# 202011AWSNP03.net
KiCad netlist of a schematic drawn in Altium Designer
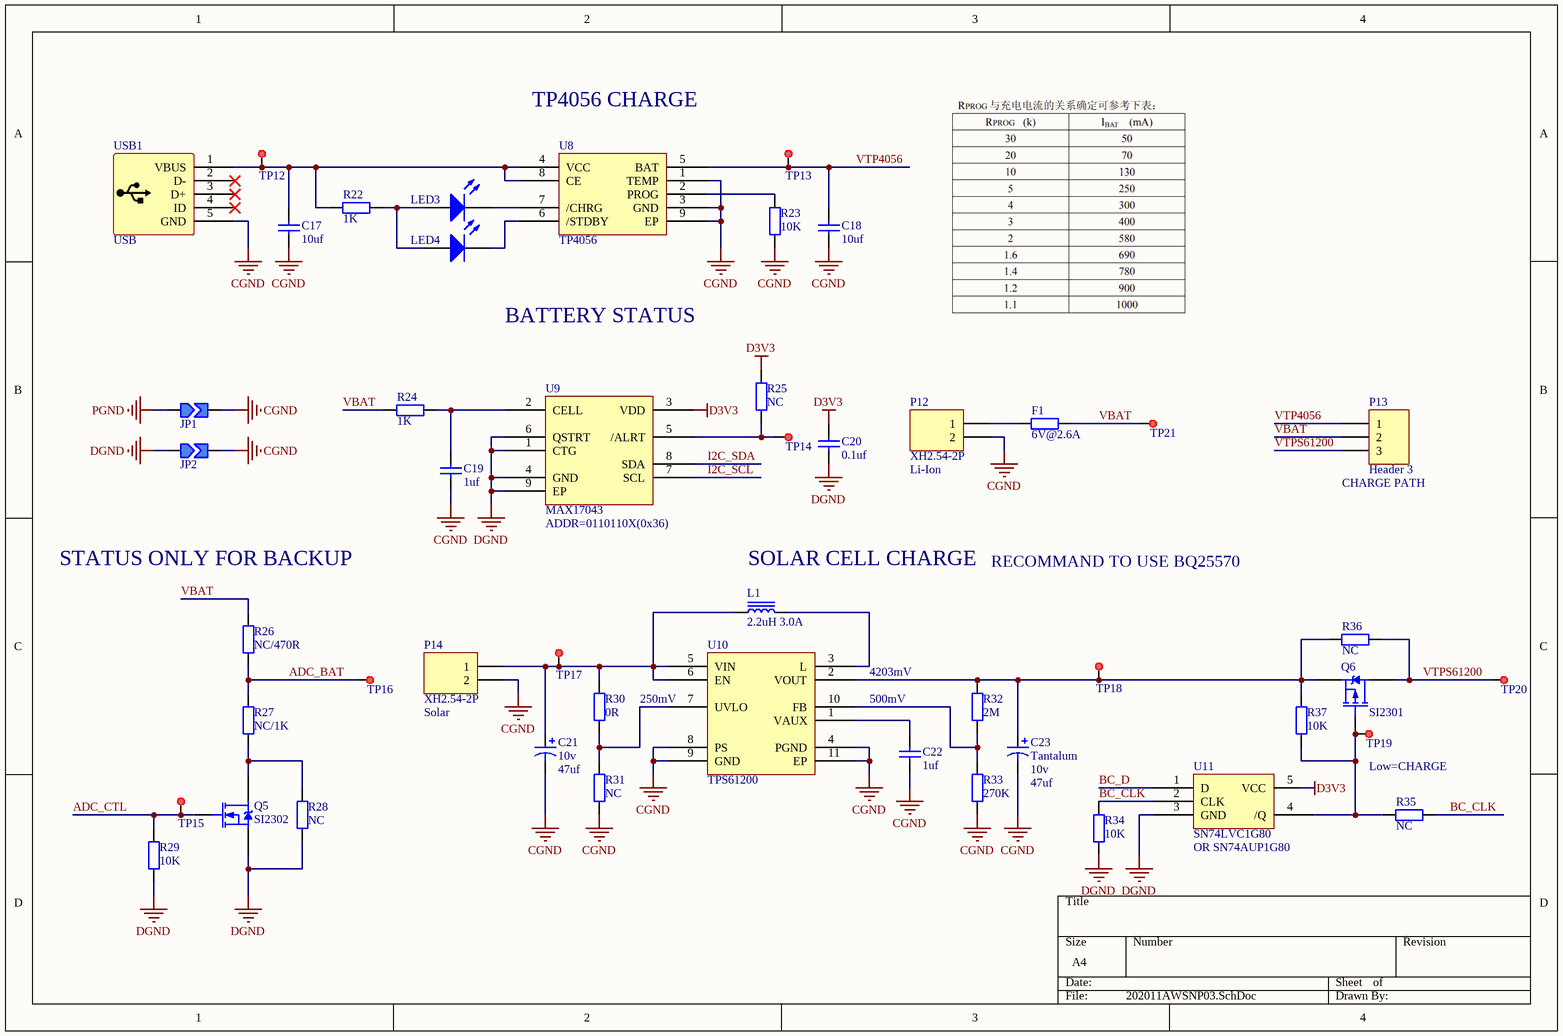
[diagram p0: 202011AWSNP03.SchDoc]

(export (version "E")
  (design (tool "Eeschema 10.0.6"))
  (components
    (comp (ref "C17")
      (value "10uf")
      (footprint "C0805")
      (fields (field (name "Comment") "Cap"))
      (libsource (lib "carrot_lib") (part "Cap"))
    )
    (comp (ref "C18")
      (value "10uf")
      (footprint "C0805")
      (fields (field (name "Comment") "Cap"))
      (libsource (lib "carrot_lib") (part "Cap"))
    )
    (comp (ref "C19")
      (value "1uf")
      (footprint "C0805")
      (fields (field (name "Comment") "Cap"))
      (libsource (lib "carrot_lib") (part "Cap"))
    )
    (comp (ref "C20")
      (value "0.1uf")
      (footprint "C0805")
      (fields (field (name "Comment") "Cap"))
      (libsource (lib "carrot_lib") (part "Cap"))
    )
    (comp (ref "C21")
      (value "47uf")
      (footprint "C4X5.4-SMD")
      (fields (field (name "VOLTAGE") "10v") (field (name "Comment") "Cap2"))
      (libsource (lib "carrot_lib") (part "Cap2"))
    )
    (comp (ref "C22")
      (value "1uf")
      (footprint "C0805")
      (fields (field (name "Comment") "Cap"))
      (libsource (lib "carrot_lib") (part "Cap"))
    )
    (comp (ref "C23")
      (value "Tantalum")
      (footprint "C1210T-3528B")
      (fields (field (name "VOLTAGE") "10v") (field (name "ALTIUM_VALUE") "47uf"))
      (libsource (lib "carrot_lib") (part "Cap-Tantalum"))
    )
    (comp (ref "F1")
      (value "6V@2.6A")
      (footprint "F1812")
      (fields (field (name "Comment") "Fuse"))
      (libsource (lib "carrot_lib") (part "Fuse"))
    )
    (comp (ref "JP1") (value "Jumper") (footprint "Jumper-2") (libsource (lib "carrot_lib") (part "Jumper")))
    (comp (ref "JP2") (value "Jumper") (footprint "Jumper-2") (libsource (lib "carrot_lib") (part "Jumper")))
    (comp (ref "L1")
      (value "2.2uH 3.0A")
      (footprint "L04042")
      (description "Magnetic-Core Inductor")
      (fields (field (name "Comment") "Inductor Iron"))
      (libsource (lib "carrot_lib") (part "Inductor Iron"))
    )
    (comp (ref "LED3") (value "LED") (footprint "LED1206") (libsource (lib "carrot_lib") (part "LED")))
    (comp (ref "LED4") (value "LED") (footprint "LED1206") (libsource (lib "carrot_lib") (part "LED")))
    (comp (ref "P12")
      (value "XH2.54-2P")
      (footprint "XH2.54-2P")
      (libsource (lib "carrot_lib") (part "XH2.54-2P"))
    )
    (comp (ref "P13")
      (value "Header 3")
      (footprint "HDR1X3")
      (description "Header, 3-Pin")
      (fields (field (name "PUBLISHER") "Altium Limited"))
      (libsource (lib "Miscellaneous Connectors") (part "Header 3"))
    )
    (comp (ref "P14")
      (value "XH2.54-2P")
      (footprint "XH2.54-2P")
      (libsource (lib "carrot_lib") (part "XH2.54-2P"))
    )
    (comp (ref "Q5")
      (value "SI2302")
      (footprint "SI2302-SOT23")
      (description "N-Channel 20 V (D-S) MOSFET")
      (libsource (lib "carrot_lib") (part "SI2302"))
    )
    (comp (ref "Q6")
      (value "SI2301")
      (footprint "SI2301-SOT23")
      (description "P-Channel 20 V (D-S) MOSFET")
      (libsource (lib "carrot_lib") (part "SI2301"))
    )
    (comp (ref "R22")
      (value "1K")
      (footprint "R0805")
      (description "电阻")
      (fields (field (name "Comment") "Res"))
      (libsource (lib "carrot_lib") (part "Res"))
    )
    (comp (ref "R23")
      (value "10K")
      (footprint "R0805")
      (description "电阻")
      (fields (field (name "Comment") "Res"))
      (libsource (lib "") (part "Res_2"))
    )
    (comp (ref "R24")
      (value "1K")
      (footprint "R0805")
      (description "电阻")
      (fields (field (name "Comment") "Res"))
      (libsource (lib "carrot_lib") (part "Res"))
    )
    (comp (ref "R25")
      (value "NC")
      (footprint "R0805")
      (description "电阻")
      (fields (field (name "Comment") "Res"))
      (libsource (lib "") (part "Res_2"))
    )
    (comp (ref "R26")
      (value "NC/470R")
      (footprint "R0805")
      (description "电阻")
      (fields (field (name "Comment") "Res"))
      (libsource (lib "") (part "Res_1"))
    )
    (comp (ref "R27")
      (value "NC/1K")
      (footprint "R0805")
      (description "电阻")
      (fields (field (name "Comment") "Res"))
      (libsource (lib "") (part "Res_1"))
    )
    (comp (ref "R28")
      (value "NC")
      (footprint "R0805")
      (description "电阻")
      (fields (field (name "Comment") "Res"))
      (libsource (lib "") (part "Res_1"))
    )
    (comp (ref "R29")
      (value "10K")
      (footprint "R0805")
      (description "电阻")
      (fields (field (name "Comment") "Res"))
      (libsource (lib "") (part "Res_1"))
    )
    (comp (ref "R30")
      (value "0R")
      (footprint "R0805")
      (description "电阻")
      (fields (field (name "Comment") "Res"))
      (libsource (lib "") (part "Res_2"))
    )
    (comp (ref "R31")
      (value "NC")
      (footprint "R0805")
      (description "电阻")
      (fields (field (name "Comment") "Res"))
      (libsource (lib "") (part "Res_2"))
    )
    (comp (ref "R32")
      (value "2M")
      (footprint "R0805")
      (description "电阻")
      (fields (field (name "Comment") "Res"))
      (libsource (lib "") (part "Res_2"))
    )
    (comp (ref "R33")
      (value "270K")
      (footprint "R0805")
      (description "电阻")
      (fields (field (name "Comment") "Res"))
      (libsource (lib "") (part "Res_2"))
    )
    (comp (ref "R34")
      (value "10K")
      (footprint "R0805")
      (description "电阻")
      (fields (field (name "Comment") "Res"))
      (libsource (lib "carrot_lib") (part "Res"))
    )
    (comp (ref "R35")
      (value "NC")
      (footprint "R0805")
      (description "电阻")
      (fields (field (name "Comment") "Res"))
      (libsource (lib "") (part "Res_2"))
    )
    (comp (ref "R36")
      (value "NC")
      (footprint "R0805")
      (description "电阻")
      (fields (field (name "Comment") "Res"))
      (libsource (lib "") (part "Res_2"))
    )
    (comp (ref "R37")
      (value "10K")
      (footprint "R0805")
      (description "电阻")
      (fields (field (name "Comment") "Res"))
      (libsource (lib "carrot_lib") (part "Res"))
    )
    (comp (ref "TP12")
      (value "TestPoint")
      (footprint "TestPoint-R30")
      (description "测试点")
      (libsource (lib "carrot_lib") (part "TestPoint"))
    )
    (comp (ref "TP13")
      (value "TestPoint")
      (footprint "TestPoint-R30")
      (description "测试点")
      (libsource (lib "carrot_lib") (part "TestPoint"))
    )
    (comp (ref "TP14")
      (value "TestPoint")
      (footprint "TestPoint-R30")
      (description "测试点")
      (libsource (lib "carrot_lib") (part "TestPoint"))
    )
    (comp (ref "TP15")
      (value "TestPoint")
      (footprint "TestPoint-R30")
      (description "测试点")
      (libsource (lib "carrot_lib") (part "TestPoint"))
    )
    (comp (ref "TP16")
      (value "TestPoint")
      (footprint "TestPoint-R30")
      (description "测试点")
      (libsource (lib "carrot_lib") (part "TestPoint"))
    )
    (comp (ref "TP17")
      (value "TestPoint")
      (footprint "TestPoint-R30")
      (description "测试点")
      (libsource (lib "carrot_lib") (part "TestPoint"))
    )
    (comp (ref "TP18")
      (value "TestPoint")
      (footprint "TestPoint-R30")
      (description "测试点")
      (libsource (lib "carrot_lib") (part "TestPoint"))
    )
    (comp (ref "TP19")
      (value "TestPoint")
      (footprint "TestPoint-R30")
      (description "测试点")
      (libsource (lib "carrot_lib") (part "TestPoint"))
    )
    (comp (ref "TP20")
      (value "TestPoint")
      (footprint "TestPoint-R30")
      (description "测试点")
      (libsource (lib "carrot_lib") (part "TestPoint"))
    )
    (comp (ref "TP21")
      (value "TestPoint")
      (footprint "TestPoint-R30")
      (description "测试点")
      (libsource (lib "carrot_lib") (part "TestPoint"))
    )
    (comp (ref "U8")
      (value "TP4056")
      (footprint "TP4056-SOIC8")
      (description "1A 线性锂离子电池充电器")
      (libsource (lib "carrot_lib") (part "TP4056"))
    )
    (comp (ref "U9")
      (value "MAX17043")
      (footprint "MAX17043-TDFN8")
      (description "1-Cell/2-Cell Fuel Gauge with ModelGauge and Low-Battery Alert")
      (libsource (lib "carrot_lib") (part "MAX17043"))
    )
    (comp (ref "U10")
      (value "TPS61200")
      (footprint "TPS61200-VSON10")
      (description "TPS61200x Low Input Voltage Synchronous Boost Converter With 1.3-A Switches")
      (libsource (lib "carrot_lib") (part "TPS61200"))
    )
    (comp (ref "U11")
      (value "SN74LVC1G80")
      (footprint "SN74LVC1G80-SC70")
      (description "Single Positive-Edge-Triggered D-Type Flip-Flop")
      (libsource (lib "carrot_lib") (part "SN74LVC1G80"))
    )
    (comp (ref "USB1") (value "USB") (footprint "USB-Mini-SMT") (libsource (lib "carrot_lib") (part "USB")))
  )
  (nets
    (net (code "1") (name "/ADC_BAT") (class "Default")
      (node (ref "R26") (pin "1") (pinfunction "1_1") (pintype "passive"))
      (node (ref "R27") (pin "2") (pinfunction "2_2") (pintype "passive"))
      (node (ref "TP16") (pin "1") (pinfunction "1_1") (pintype "passive"))
    )
    (net (code "2") (name "/ADC_CTL") (class "Default")
      (node (ref "Q5") (pin "1") (pinfunction "G_1") (pintype "passive"))
      (node (ref "R29") (pin "2") (pinfunction "2_2") (pintype "passive"))
      (node (ref "TP15") (pin "1") (pinfunction "1_1") (pintype "passive"))
    )
    (net (code "3") (name "/BC_CLK") (class "Default")
      (node (ref "R34") (pin "1") (pinfunction "1_1") (pintype "passive"))
      (node (ref "R35") (pin "1") (pinfunction "1_1") (pintype "passive"))
      (node (ref "U11") (pin "2") (pinfunction "CLK_2") (pintype "passive"))
    )
    (net (code "4") (name "/BC_D") (class "Default")
      (node (ref "U11") (pin "1") (pinfunction "D_1") (pintype "passive"))
    )
    (net (code "5") (name "/I2C_SCL") (class "Default")
      (node (ref "U9") (pin "7") (pinfunction "SCL_7") (pintype "passive"))
    )
    (net (code "6") (name "/I2C_SDA") (class "Default")
      (node (ref "U9") (pin "8") (pinfunction "SDA_8") (pintype "passive"))
    )
    (net (code "7") (name "/VBAT") (class "Default")
      (node (ref "F1") (pin "2") (pinfunction "2_2") (pintype "passive"))
      (node (ref "P13") (pin "2") (pinfunction "2_2") (pintype "passive"))
      (node (ref "R24") (pin "2") (pinfunction "2_2") (pintype "passive"))
      (node (ref "R26") (pin "2") (pinfunction "2_2") (pintype "passive"))
      (node (ref "TP21") (pin "1") (pinfunction "1_1") (pintype "passive"))
    )
    (net (code "8") (name "/VTP4056") (class "Default")
      (node (ref "C18") (pin "2") (pinfunction "2_2") (pintype "passive"))
      (node (ref "P13") (pin "1") (pinfunction "1_1") (pintype "passive"))
      (node (ref "TP13") (pin "1") (pinfunction "1_1") (pintype "passive"))
      (node (ref "U8") (pin "5") (pinfunction "BAT_5") (pintype "passive"))
    )
    (net (code "9") (name "/VTPS61200") (class "Default")
      (node (ref "P13") (pin "3") (pinfunction "3_3") (pintype "passive"))
      (node (ref "Q6") (pin "3") (pinfunction "D_3") (pintype "passive"))
      (node (ref "R36") (pin "1") (pinfunction "1_1") (pintype "passive"))
      (node (ref "TP20") (pin "1") (pinfunction "1_1") (pintype "passive"))
    )
    (net (code "10") (name "CGND") (class "Default")
      (node (ref "C17") (pin "1") (pinfunction "1_1") (pintype "passive"))
      (node (ref "C18") (pin "1") (pinfunction "1_1") (pintype "passive"))
      (node (ref "C19") (pin "1") (pinfunction "1_1") (pintype "passive"))
      (node (ref "C21") (pin "2") (pinfunction "2_2") (pintype "passive"))
      (node (ref "C22") (pin "1") (pinfunction "1_1") (pintype "passive"))
      (node (ref "C23") (pin "2") (pinfunction "2_2") (pintype "passive"))
      (node (ref "JP1") (pin "2") (pinfunction "2_2") (pintype "passive"))
      (node (ref "JP2") (pin "2") (pinfunction "2_2") (pintype "passive"))
      (node (ref "P12") (pin "2") (pinfunction "2_2") (pintype "passive"))
      (node (ref "P14") (pin "2") (pinfunction "2_2") (pintype "passive"))
      (node (ref "R23") (pin "2") (pinfunction "2_2") (pintype "passive"))
      (node (ref "R31") (pin "2") (pinfunction "2_2") (pintype "passive"))
      (node (ref "R33") (pin "2") (pinfunction "2_2") (pintype "passive"))
      (node (ref "U10") (pin "11") (pinfunction "EP_11") (pintype "passive"))
      (node (ref "U10") (pin "4") (pinfunction "PGND_4") (pintype "passive"))
      (node (ref "U10") (pin "8") (pinfunction "PS_8") (pintype "passive"))
      (node (ref "U10") (pin "9") (pinfunction "GND_9") (pintype "passive"))
      (node (ref "U8") (pin "1") (pinfunction "TEMP_1") (pintype "passive"))
      (node (ref "U8") (pin "3") (pinfunction "GND_3") (pintype "passive"))
      (node (ref "U8") (pin "9") (pinfunction "EP_9") (pintype "passive"))
      (node (ref "USB1") (pin "5") (pinfunction "GND_5") (pintype "passive"))
    )
    (net (code "11") (name "D3V3") (class "Default")
      (node (ref "C20") (pin "2") (pinfunction "2_2") (pintype "passive"))
      (node (ref "R25") (pin "1") (pinfunction "1_1") (pintype "passive"))
      (node (ref "U11") (pin "5") (pinfunction "VCC_5") (pintype "passive"))
      (node (ref "U9") (pin "3") (pinfunction "VDD_3") (pintype "passive"))
    )
    (net (code "12") (name "DGND") (class "Default")
      (node (ref "C20") (pin "1") (pinfunction "1_1") (pintype "passive"))
      (node (ref "JP2") (pin "1") (pinfunction "1_1") (pintype "passive"))
      (node (ref "Q5") (pin "2") (pinfunction "S_2") (pintype "passive"))
      (node (ref "R28") (pin "1") (pinfunction "1_1") (pintype "passive"))
      (node (ref "R29") (pin "1") (pinfunction "1_1") (pintype "passive"))
      (node (ref "R34") (pin "2") (pinfunction "2_2") (pintype "passive"))
      (node (ref "U11") (pin "3") (pinfunction "GND_3") (pintype "passive"))
      (node (ref "U9") (pin "1") (pinfunction "CTG_1") (pintype "passive"))
      (node (ref "U9") (pin "4") (pinfunction "GND_4") (pintype "passive"))
      (node (ref "U9") (pin "6") (pinfunction "QSTRT_6") (pintype "passive"))
      (node (ref "U9") (pin "9") (pinfunction "EP_9") (pintype "passive"))
    )
    (net (code "13") (name "Net-(F1-Pad1)") (class "Default")
      (node (ref "F1") (pin "1") (pinfunction "1_1") (pintype "passive"))
      (node (ref "P12") (pin "1") (pinfunction "1_1") (pintype "passive"))
    )
    (net (code "14") (name "Net-(LED3-A)") (class "Default")
      (node (ref "LED3") (pin "1") (pinfunction "A_1") (pintype "passive"))
      (node (ref "LED4") (pin "1") (pinfunction "A_1") (pintype "passive"))
      (node (ref "R22") (pin "1") (pinfunction "1_1") (pintype "passive"))
    )
    (net (code "15") (name "Net-(LED3-K)") (class "Default")
      (node (ref "LED3") (pin "2") (pinfunction "K_2") (pintype "passive"))
      (node (ref "U8") (pin "7") (pinfunction "/CHRG_7") (pintype "passive"))
    )
    (net (code "16") (name "Net-(LED4-K)") (class "Default")
      (node (ref "LED4") (pin "2") (pinfunction "K_2") (pintype "passive"))
      (node (ref "U8") (pin "6") (pinfunction "/STDBY_6") (pintype "passive"))
    )
    (net (code "17") (name "Net-(Q5-D)") (class "Default")
      (node (ref "Q5") (pin "3") (pinfunction "D_3") (pintype "passive"))
      (node (ref "R27") (pin "1") (pinfunction "1_1") (pintype "passive"))
      (node (ref "R28") (pin "2") (pinfunction "2_2") (pintype "passive"))
    )
    (net (code "18") (name "Net-(Q6-G)") (class "Default")
      (node (ref "Q6") (pin "1") (pinfunction "G_1") (pintype "passive"))
      (node (ref "R35") (pin "2") (pinfunction "2_2") (pintype "passive"))
      (node (ref "R37") (pin "2") (pinfunction "2_2") (pintype "passive"))
      (node (ref "TP19") (pin "1") (pinfunction "1_1") (pintype "passive"))
      (node (ref "U11") (pin "4") (pinfunction "/Q_4") (pintype "passive"))
    )
    (net (code "19") (name "Net-(Q6-S)") (class "Default")
      (node (ref "C23") (pin "1") (pinfunction "1_1") (pintype "passive"))
      (node (ref "Q6") (pin "2") (pinfunction "S_2") (pintype "passive"))
      (node (ref "R32") (pin "1") (pinfunction "1_1") (pintype "passive"))
      (node (ref "R36") (pin "2") (pinfunction "2_2") (pintype "passive"))
      (node (ref "R37") (pin "1") (pinfunction "1_1") (pintype "passive"))
      (node (ref "TP18") (pin "1") (pinfunction "1_1") (pintype "passive"))
      (node (ref "U10") (pin "2") (pinfunction "VOUT_2") (pintype "passive"))
    )
    (net (code "20") (name "Net-(U8-CE)") (class "Default")
      (node (ref "C17") (pin "2") (pinfunction "2_2") (pintype "passive"))
      (node (ref "R22") (pin "2") (pinfunction "2_2") (pintype "passive"))
      (node (ref "TP12") (pin "1") (pinfunction "1_1") (pintype "passive"))
      (node (ref "U8") (pin "4") (pinfunction "VCC_4") (pintype "passive"))
      (node (ref "U8") (pin "8") (pinfunction "CE_8") (pintype "passive"))
      (node (ref "USB1") (pin "1") (pinfunction "VBUS_1") (pintype "passive"))
    )
    (net (code "21") (name "Net-(U8-PROG)") (class "Default")
      (node (ref "R23") (pin "1") (pinfunction "1_1") (pintype "passive"))
      (node (ref "U8") (pin "2") (pinfunction "PROG_2") (pintype "passive"))
    )
    (net (code "22") (name "Net-(U9-CELL)") (class "Default")
      (node (ref "C19") (pin "2") (pinfunction "2_2") (pintype "passive"))
      (node (ref "R24") (pin "1") (pinfunction "1_1") (pintype "passive"))
      (node (ref "U9") (pin "2") (pinfunction "CELL_2") (pintype "passive"))
    )
    (net (code "23") (name "Net-(U9-{slash}ALRT)") (class "Default")
      (node (ref "R25") (pin "2") (pinfunction "2_2") (pintype "passive"))
      (node (ref "TP14") (pin "1") (pinfunction "1_1") (pintype "passive"))
      (node (ref "U9") (pin "5") (pinfunction "/ALRT_5") (pintype "passive"))
    )
    (net (code "24") (name "Net-(U10-EN)") (class "Default")
      (node (ref "C21") (pin "1") (pinfunction "1_1") (pintype "passive"))
      (node (ref "L1") (pin "1") (pinfunction "1_1") (pintype "passive"))
      (node (ref "P14") (pin "1") (pinfunction "1_1") (pintype "passive"))
      (node (ref "R30") (pin "1") (pinfunction "1_1") (pintype "passive"))
      (node (ref "TP17") (pin "1") (pinfunction "1_1") (pintype "passive"))
      (node (ref "U10") (pin "5") (pinfunction "VIN_5") (pintype "passive"))
      (node (ref "U10") (pin "6") (pinfunction "EN_6") (pintype "passive"))
    )
    (net (code "25") (name "Net-(U10-FB)") (class "Default")
      (node (ref "R32") (pin "2") (pinfunction "2_2") (pintype "passive"))
      (node (ref "R33") (pin "1") (pinfunction "1_1") (pintype "passive"))
      (node (ref "U10") (pin "10") (pinfunction "FB_10") (pintype "passive"))
    )
    (net (code "26") (name "Net-(U10-L)") (class "Default")
      (node (ref "L1") (pin "2") (pinfunction "2_2") (pintype "passive"))
      (node (ref "U10") (pin "3") (pinfunction "L_3") (pintype "passive"))
    )
    (net (code "27") (name "Net-(U10-UVLO)") (class "Default")
      (node (ref "R30") (pin "2") (pinfunction "2_2") (pintype "passive"))
      (node (ref "R31") (pin "1") (pinfunction "1_1") (pintype "passive"))
      (node (ref "U10") (pin "7") (pinfunction "UVLO_7") (pintype "passive"))
    )
    (net (code "28") (name "Net-(U10-VAUX)") (class "Default")
      (node (ref "C22") (pin "2") (pinfunction "2_2") (pintype "passive"))
      (node (ref "U10") (pin "1") (pinfunction "VAUX_1") (pintype "passive"))
    )
    (net (code "29") (name "PGND") (class "Default")
      (node (ref "JP1") (pin "1") (pinfunction "1_1") (pintype "passive"))
    )
    (net (code "30") (name "unconnected-(USB1-D+-Pad3)") (class "Default")
      (node (ref "USB1") (pin "3") (pinfunction "D+_3") (pintype "passive+no_connect"))
    )
    (net (code "31") (name "unconnected-(USB1-D--Pad2)") (class "Default")
      (node (ref "USB1") (pin "2") (pinfunction "D-_2") (pintype "passive+no_connect"))
    )
    (net (code "32") (name "unconnected-(USB1-ID-Pad4)") (class "Default")
      (node (ref "USB1") (pin "4") (pinfunction "ID_4") (pintype "passive+no_connect"))
    )
  )
)
